# 5V_SPI_Oled_Rev1_1.net
KiCad netlist of a schematic drawn in Altium Designer
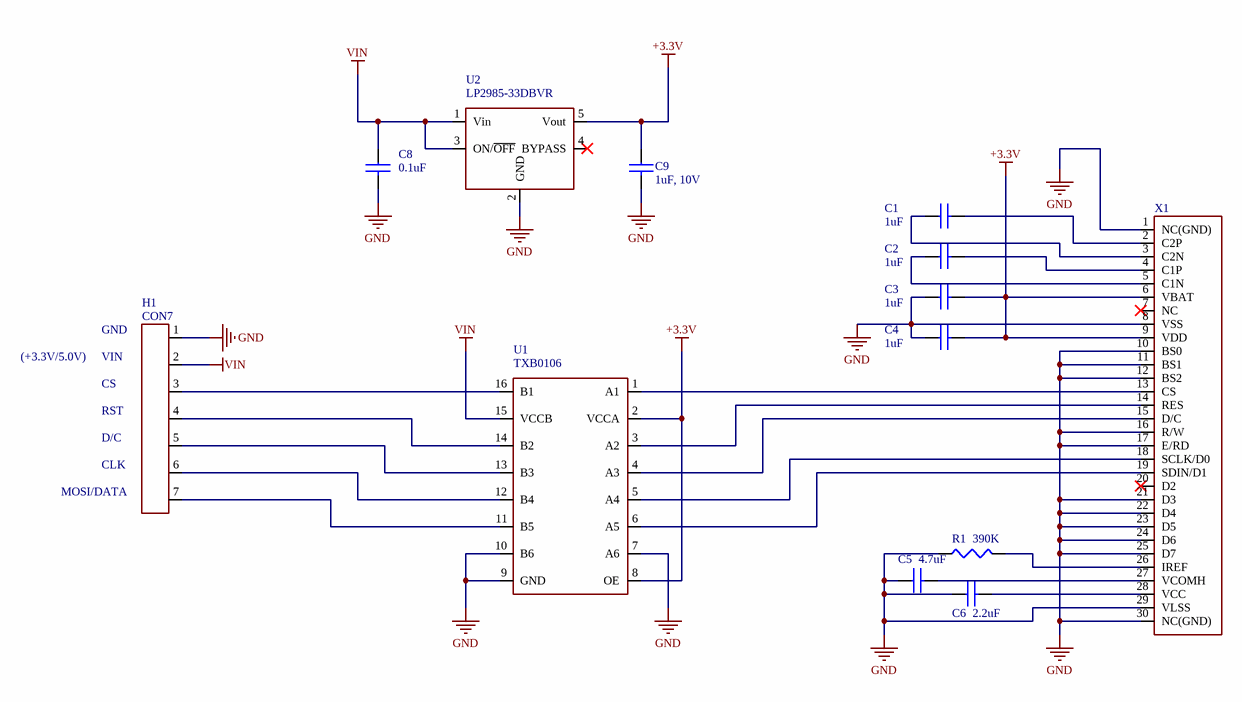
[diagram p0: 5V_SPI_Oled_Rev1.1.SchDoc]

(export (version "E")
  (design (tool "Eeschema 10.0.6"))
  (components
    (comp (ref "C1")
      (value "1uF")
      (footprint "CAPC1608X90N")
      (description "CAP 0603")
      (libsource (lib "Parts_Library") (part "CAP_0603"))
    )
    (comp (ref "C2")
      (value "1uF")
      (footprint "CAPC1608X90N")
      (description "CAP 0603")
      (libsource (lib "Parts_Library") (part "CAP_0603"))
    )
    (comp (ref "C3")
      (value "1uF")
      (footprint "CAPC1608X90N")
      (description "CAP 0603")
      (libsource (lib "Parts_Library") (part "CAP_0603"))
    )
    (comp (ref "C4")
      (value "1uF")
      (footprint "CAPC1608X90N")
      (description "CAP 0603")
      (libsource (lib "Parts_Library") (part "CAP_0603"))
    )
    (comp (ref "C5")
      (value "4.7uF")
      (footprint "CAPC1608X90N")
      (description "CAP 0603")
      (libsource (lib "Parts_Library") (part "CAP_0603"))
    )
    (comp (ref "C6")
      (value "2.2uF")
      (footprint "CAPC1608X90N")
      (description "CAP 0603")
      (libsource (lib "Parts_Library") (part "CAP_0603"))
    )
    (comp (ref "C8")
      (value "0.1uF")
      (footprint "CAPC1608X90N")
      (description "CAP 0603")
      (libsource (lib "Parts_Library") (part "CAP_0603"))
    )
    (comp (ref "C9")
      (value "1uF, 10V")
      (footprint "CAPC1608X90N")
      (description "CAP CER 1UF 10V 10% X7R 0603")
      (fields (field (name "EXACT PART NUMBER") "C1608X7R1A105K") (field (name "MANUFACTURER") "TDK Corp"))
      (libsource (lib "Parts_Library") (part "C1608X7R1A105K"))
    )
    (comp (ref "H1")
      (value "CON7")
      (footprint "HDR1X7")
      (description "CONN HEADER 7POS .100\" PADS")
      (fields (field (name "PARTNUMBER") "PADS"))
      (libsource (lib "MAR") (part "CON7"))
    )
    (comp (ref "R1")
      (value "390K")
      (footprint "RESC1608X55N")
      (description "RES 0603")
      (libsource (lib "Parts_Library") (part "RES_0603"))
    )
    (comp (ref "U1")
      (value "TXB0106")
      (footprint "SOP65P602X173-16N")
      (description "IC XLATR 6B BIDIR V-LVL 16TSSOP")
      (fields (field (name "MANUFACTURER") "Texas Instruments") (field (name "PARTNUMBER") "TXB0106IPWRQ1"))
      (libsource (lib "MAR") (part "TXB0106IPWRQ1"))
    )
    (comp (ref "U2")
      (value "LP2985-33DBVR")
      (footprint "SOT95P280X144-5N")
      (description "IC REG LDO 3.3V .15A SOT23-5")
      (fields (field (name "MANUFACTURER") "Texas Instruments"))
      (libsource (lib "Parts_Library") (part "LP2985-33DBVR"))
    )
    (comp (ref "X1")
      (value "OLED_GLASS")
      (footprint "OLED_GLASS")
      (libsource (lib "Parts_Library") (part "OLED_GLASS"))
    )
  )
  (nets
    (net (code "1") (name "+3.3V") (class "Default")
      (node (ref "C3") (pin "2") (pinfunction "2_2") (pintype "passive"))
      (node (ref "C4") (pin "2") (pinfunction "2_2") (pintype "passive"))
      (node (ref "C9") (pin "1") (pinfunction "1_1") (pintype "passive"))
      (node (ref "U1") (pin "2") (pinfunction "VCCA_2") (pintype "power_in"))
      (node (ref "U1") (pin "8") (pinfunction "OE_8") (pintype "passive"))
      (node (ref "U2") (pin "5") (pinfunction "Vout_5") (pintype "passive"))
      (node (ref "X1") (pin "6") (pinfunction "VBAT_6") (pintype "passive"))
      (node (ref "X1") (pin "9") (pinfunction "VDD_9") (pintype "passive"))
    )
    (net (code "2") (name "GND") (class "Default")
      (node (ref "C3") (pin "1") (pinfunction "1_1") (pintype "passive"))
      (node (ref "C4") (pin "1") (pinfunction "1_1") (pintype "passive"))
      (node (ref "C5") (pin "1") (pinfunction "1_1") (pintype "passive"))
      (node (ref "C6") (pin "1") (pinfunction "1_1") (pintype "passive"))
      (node (ref "C8") (pin "2") (pinfunction "2_2") (pintype "passive"))
      (node (ref "C9") (pin "2") (pinfunction "2_2") (pintype "passive"))
      (node (ref "H1") (pin "1") (pintype "passive"))
      (node (ref "R1") (pin "1") (pinfunction "1_1") (pintype "passive"))
      (node (ref "U1") (pin "10") (pinfunction "B6_10") (pintype "passive"))
      (node (ref "U1") (pin "7") (pinfunction "A6_7") (pintype "passive"))
      (node (ref "U1") (pin "9") (pinfunction "GND_9") (pintype "power_in"))
      (node (ref "U2") (pin "2") (pinfunction "GND_2") (pintype "power_in"))
      (node (ref "X1") (pin "1") (pinfunction "NC(GND)_1") (pintype "passive"))
      (node (ref "X1") (pin "10") (pinfunction "BS0_10") (pintype "passive"))
      (node (ref "X1") (pin "11") (pinfunction "BS1_11") (pintype "passive"))
      (node (ref "X1") (pin "12") (pinfunction "BS2_12") (pintype "passive"))
      (node (ref "X1") (pin "16") (pinfunction "R/W_16") (pintype "passive"))
      (node (ref "X1") (pin "17") (pinfunction "E/RD_17") (pintype "passive"))
      (node (ref "X1") (pin "21") (pinfunction "D3_21") (pintype "passive"))
      (node (ref "X1") (pin "22") (pinfunction "D4_22") (pintype "passive"))
      (node (ref "X1") (pin "23") (pinfunction "D5_23") (pintype "passive"))
      (node (ref "X1") (pin "24") (pinfunction "D6_24") (pintype "passive"))
      (node (ref "X1") (pin "25") (pinfunction "D7_25") (pintype "passive"))
      (node (ref "X1") (pin "29") (pinfunction "VLSS_29") (pintype "passive"))
      (node (ref "X1") (pin "30") (pinfunction "NC(GND)_30") (pintype "passive"))
      (node (ref "X1") (pin "8") (pinfunction "VSS_8") (pintype "passive"))
    )
    (net (code "3") (name "Net-(U1-A1)") (class "Default")
      (node (ref "U1") (pin "1") (pinfunction "A1_1") (pintype "passive"))
      (node (ref "X1") (pin "13") (pinfunction "CS_13") (pintype "passive"))
    )
    (net (code "4") (name "Net-(U1-A2)") (class "Default")
      (node (ref "U1") (pin "3") (pinfunction "A2_3") (pintype "passive"))
      (node (ref "X1") (pin "14") (pinfunction "RES_14") (pintype "passive"))
    )
    (net (code "5") (name "Net-(U1-A3)") (class "Default")
      (node (ref "U1") (pin "4") (pinfunction "A3_4") (pintype "passive"))
      (node (ref "X1") (pin "15") (pinfunction "D/C_15") (pintype "passive"))
    )
    (net (code "6") (name "Net-(U1-A4)") (class "Default")
      (node (ref "U1") (pin "5") (pinfunction "A4_5") (pintype "passive"))
      (node (ref "X1") (pin "18") (pinfunction "SCLK/D0_18") (pintype "passive"))
    )
    (net (code "7") (name "Net-(U1-A5)") (class "Default")
      (node (ref "U1") (pin "6") (pinfunction "A5_6") (pintype "passive"))
      (node (ref "X1") (pin "19") (pinfunction "SDIN/D1_19") (pintype "passive"))
    )
    (net (code "8") (name "Net-(U1-B1)") (class "Default")
      (node (ref "H1") (pin "3") (pintype "passive"))
      (node (ref "U1") (pin "16") (pinfunction "B1_16") (pintype "passive"))
    )
    (net (code "9") (name "Net-(U1-B2)") (class "Default")
      (node (ref "H1") (pin "4") (pintype "passive"))
      (node (ref "U1") (pin "14") (pinfunction "B2_14") (pintype "passive"))
    )
    (net (code "10") (name "Net-(U1-B3)") (class "Default")
      (node (ref "H1") (pin "5") (pintype "passive"))
      (node (ref "U1") (pin "13") (pinfunction "B3_13") (pintype "passive"))
    )
    (net (code "11") (name "Net-(U1-B4)") (class "Default")
      (node (ref "H1") (pin "6") (pintype "passive"))
      (node (ref "U1") (pin "12") (pinfunction "B4_12") (pintype "passive"))
    )
    (net (code "12") (name "Net-(U1-B5)") (class "Default")
      (node (ref "H1") (pin "7") (pintype "passive"))
      (node (ref "U1") (pin "11") (pinfunction "B5_11") (pintype "passive"))
    )
    (net (code "13") (name "Net-(X1-C1N)") (class "Default")
      (node (ref "C2") (pin "1") (pinfunction "1_1") (pintype "passive"))
      (node (ref "X1") (pin "5") (pinfunction "C1N_5") (pintype "passive"))
    )
    (net (code "14") (name "Net-(X1-C1P)") (class "Default")
      (node (ref "C2") (pin "2") (pinfunction "2_2") (pintype "passive"))
      (node (ref "X1") (pin "4") (pinfunction "C1P_4") (pintype "passive"))
    )
    (net (code "15") (name "Net-(X1-C2N)") (class "Default")
      (node (ref "C1") (pin "1") (pinfunction "1_1") (pintype "passive"))
      (node (ref "X1") (pin "3") (pinfunction "C2N_3") (pintype "passive"))
    )
    (net (code "16") (name "Net-(X1-C2P)") (class "Default")
      (node (ref "C1") (pin "2") (pinfunction "2_2") (pintype "passive"))
      (node (ref "X1") (pin "2") (pinfunction "C2P_2") (pintype "passive"))
    )
    (net (code "17") (name "Net-(X1-IREF)") (class "Default")
      (node (ref "R1") (pin "2") (pinfunction "2_2") (pintype "passive"))
      (node (ref "X1") (pin "26") (pinfunction "IREF_26") (pintype "passive"))
    )
    (net (code "18") (name "Net-(X1-VCC)") (class "Default")
      (node (ref "C6") (pin "2") (pinfunction "2_2") (pintype "passive"))
      (node (ref "X1") (pin "28") (pinfunction "VCC_28") (pintype "passive"))
    )
    (net (code "19") (name "Net-(X1-VCOMH)") (class "Default")
      (node (ref "C5") (pin "2") (pinfunction "2_2") (pintype "passive"))
      (node (ref "X1") (pin "27") (pinfunction "VCOMH_27") (pintype "passive"))
    )
    (net (code "20") (name "VIN") (class "Default")
      (node (ref "C8") (pin "1") (pinfunction "1_1") (pintype "passive"))
      (node (ref "H1") (pin "2") (pintype "passive"))
      (node (ref "U1") (pin "15") (pinfunction "VCCB_15") (pintype "power_in"))
      (node (ref "U2") (pin "1") (pinfunction "Vin_1") (pintype "passive"))
      (node (ref "U2") (pin "3") (pinfunction "ON/~{OFF}_3") (pintype "passive"))
    )
    (net (code "21") (name "unconnected-(U2-BYPASS-Pad4)") (class "Default")
      (node (ref "U2") (pin "4") (pinfunction "BYPASS_4") (pintype "passive+no_connect"))
    )
    (net (code "22") (name "unconnected-(X1-D2-Pad20)") (class "Default")
      (node (ref "X1") (pin "20") (pinfunction "D2_20") (pintype "passive+no_connect"))
    )
    (net (code "23") (name "unconnected-(X1-NC-Pad7)") (class "Default")
      (node (ref "X1") (pin "7") (pinfunction "NC_7") (pintype "passive+no_connect"))
    )
  )
)
